# AtmegBROKE.net
KiCad netlist of a schematic drawn in EAGLE
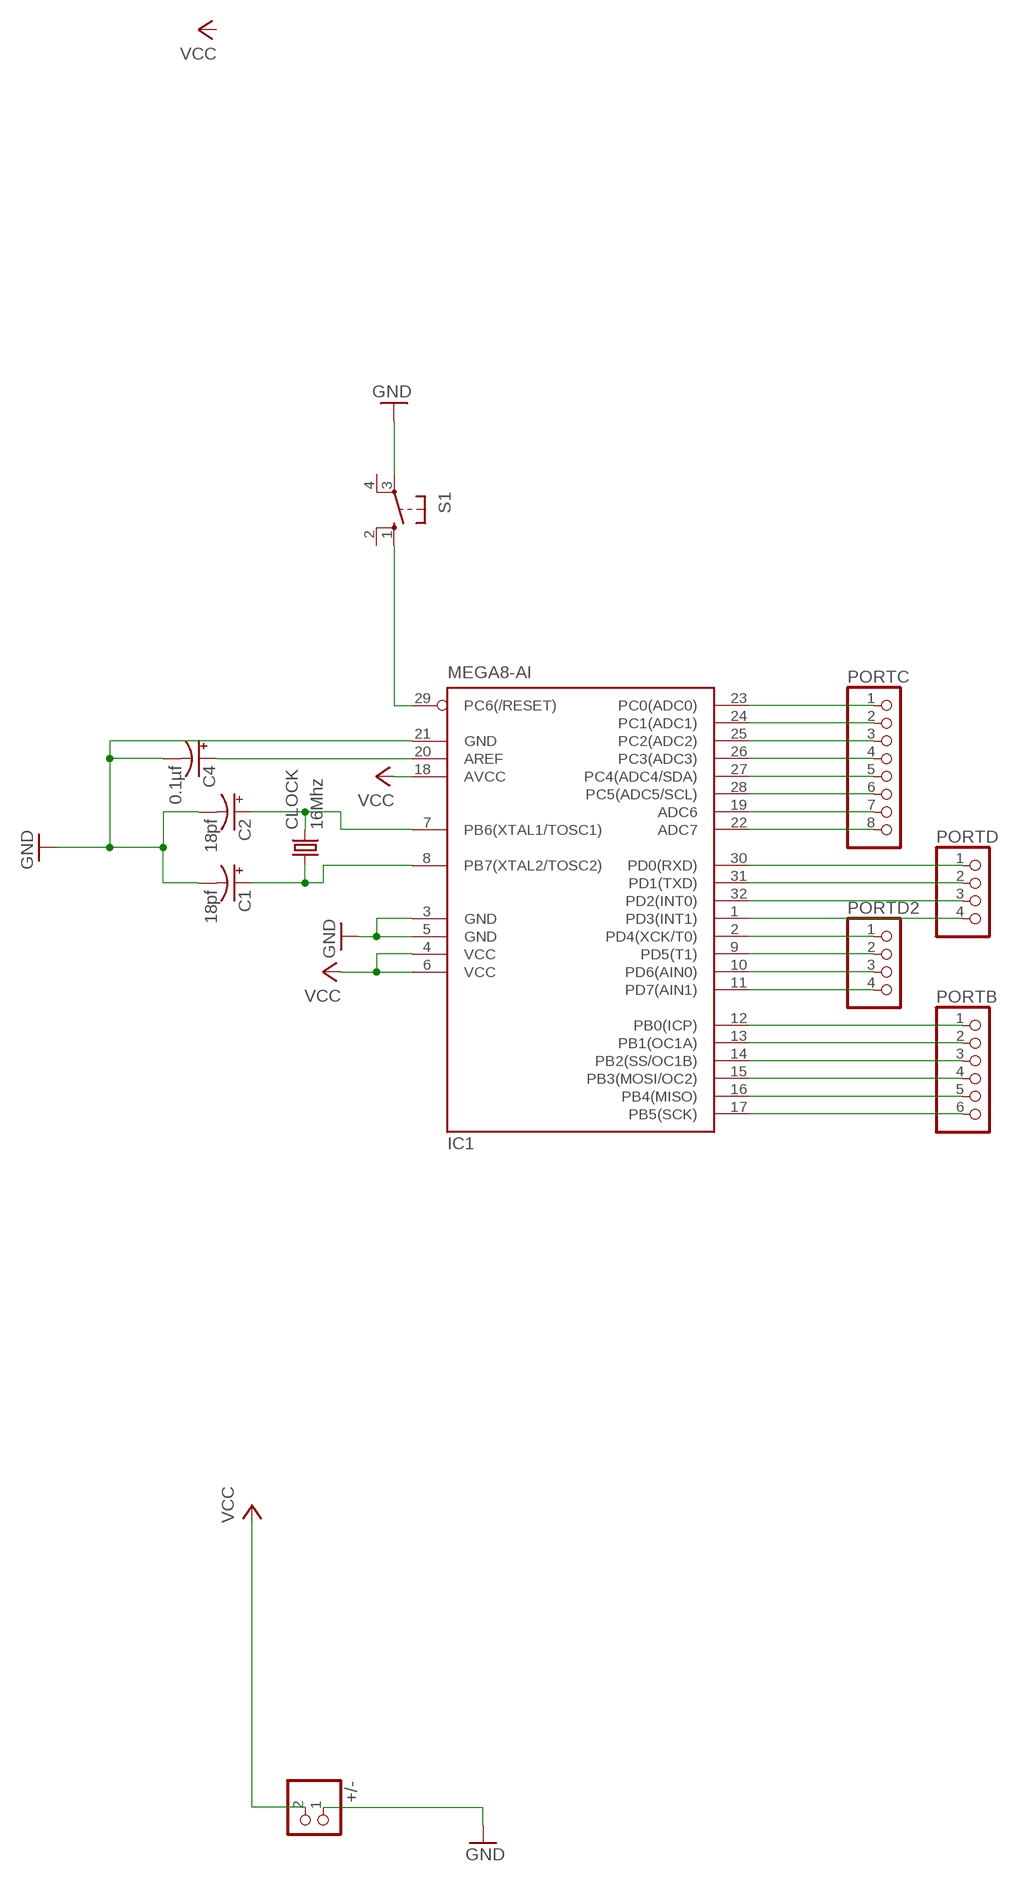
[diagram p0: schematic, sheet 1]

(export (version "E")
  (design (tool "Eeschema 10.0.6"))
  (components
    (comp (ref "+/-")
      (value "PINHD-1X2")
      (footprint "eagle-import:1X02")
      (libsource (lib "eagle-import") (part "PINHD-1X2"))
    )
    (comp (ref "C1")
      (value "18pf")
      (footprint "eagle-import:SMC_Z")
      (libsource (lib "eagle-import") (part "CPOL-USSMCZ"))
    )
    (comp (ref "C2")
      (value "18pf")
      (footprint "eagle-import:SMC_Z")
      (libsource (lib "eagle-import") (part "CPOL-USSMCZ"))
    )
    (comp (ref "C4")
      (value "0.1µf")
      (footprint "eagle-import:SMC_Z")
      (libsource (lib "eagle-import") (part "CPOL-USSMCZ"))
    )
    (comp (ref "CLOCK")
      (value "16Mhz")
      (footprint "eagle-import:HC49UP")
      (libsource (lib "eagle-import") (part "CRYSTALHC49UP"))
    )
    (comp (ref "IC1")
      (value "MEGA8-AI")
      (footprint "eagle-import:TQFP32-08")
      (fields (field (name "MPN") "ATMEGA8-16AU"))
      (libsource (lib "eagle-import") (part "MEGA8-AI"))
    )
    (comp (ref "PORTB")
      (value "PINHD-1X6")
      (footprint "eagle-import:1X06")
      (libsource (lib "eagle-import") (part "PINHD-1X6"))
    )
    (comp (ref "PORTC")
      (value "PINHD-1X8")
      (footprint "eagle-import:1X08")
      (libsource (lib "eagle-import") (part "PINHD-1X8"))
    )
    (comp (ref "PORTD")
      (value "PINHD-1X4")
      (footprint "eagle-import:1X04")
      (libsource (lib "eagle-import") (part "PINHD-1X4"))
    )
    (comp (ref "PORTD2")
      (value "PINHD-1X4")
      (footprint "eagle-import:1X04")
      (libsource (lib "eagle-import") (part "PINHD-1X4"))
    )
    (comp (ref "S1")
      (value "10-XX")
      (footprint "eagle-import:B3F-10XX")
      (fields (field (name "MPN") "B3F-1000"))
      (libsource (lib "eagle-import") (part "10-XX"))
    )
  )
  (nets
    (net (code "1") (name "GND") (class "Default")
      (node (ref "+/-") (pin "1") (pinfunction "1_1") (pintype "passive"))
      (node (ref "C1") (pin "-") (pinfunction "-_-") (pintype "passive"))
      (node (ref "C2") (pin "-") (pinfunction "-_-") (pintype "passive"))
      (node (ref "C4") (pin "-") (pinfunction "-_-") (pintype "passive"))
      (node (ref "IC1") (pin "21") (pinfunction "GND_21") (pintype "power_in"))
      (node (ref "IC1") (pin "3") (pinfunction "GND_3") (pintype "power_in"))
      (node (ref "IC1") (pin "5") (pinfunction "GND_5") (pintype "power_in"))
      (node (ref "S1") (pin "3") (pinfunction "P_3") (pintype "passive"))
    )
    (net (code "2") (name "Net-(IC1-ADC6)") (class "Default")
      (node (ref "IC1") (pin "19") (pinfunction "ADC6_19") (pintype "bidirectional"))
      (node (ref "PORTC") (pin "7") (pinfunction "7_7") (pintype "passive"))
    )
    (net (code "3") (name "Net-(IC1-ADC7)") (class "Default")
      (node (ref "IC1") (pin "22") (pinfunction "ADC7_22") (pintype "bidirectional"))
      (node (ref "PORTC") (pin "8") (pinfunction "8_8") (pintype "passive"))
    )
    (net (code "4") (name "Net-(IC1-AREF)") (class "Default")
      (node (ref "C4") (pin "+") (pinfunction "+_+") (pintype "passive"))
      (node (ref "IC1") (pin "20") (pinfunction "AREF_20") (pintype "passive"))
    )
    (net (code "5") (name "Net-(IC1-PB0(ICP))") (class "Default")
      (node (ref "IC1") (pin "12") (pinfunction "PB0(ICP)_12") (pintype "bidirectional"))
      (node (ref "PORTB") (pin "1") (pinfunction "1_1") (pintype "passive"))
    )
    (net (code "6") (name "Net-(IC1-PB1(OC1A))") (class "Default")
      (node (ref "IC1") (pin "13") (pinfunction "PB1(OC1A)_13") (pintype "bidirectional"))
      (node (ref "PORTB") (pin "2") (pinfunction "2_2") (pintype "passive"))
    )
    (net (code "7") (name "Net-(IC1-PB2(SS{slash}OC1B))") (class "Default")
      (node (ref "IC1") (pin "14") (pinfunction "PB2(SS/OC1B)_14") (pintype "bidirectional"))
      (node (ref "PORTB") (pin "3") (pinfunction "3_3") (pintype "passive"))
    )
    (net (code "8") (name "Net-(IC1-PB3(MOSI{slash}OC2))") (class "Default")
      (node (ref "IC1") (pin "15") (pinfunction "PB3(MOSI/OC2)_15") (pintype "bidirectional"))
      (node (ref "PORTB") (pin "4") (pinfunction "4_4") (pintype "passive"))
    )
    (net (code "9") (name "Net-(IC1-PB4(MISO))") (class "Default")
      (node (ref "IC1") (pin "16") (pinfunction "PB4(MISO)_16") (pintype "bidirectional"))
      (node (ref "PORTB") (pin "5") (pinfunction "5_5") (pintype "passive"))
    )
    (net (code "10") (name "Net-(IC1-PB5(SCK))") (class "Default")
      (node (ref "IC1") (pin "17") (pinfunction "PB5(SCK)_17") (pintype "bidirectional"))
      (node (ref "PORTB") (pin "6") (pinfunction "6_6") (pintype "passive"))
    )
    (net (code "11") (name "Net-(IC1-PB6(XTAL1{slash}TOSC1))") (class "Default")
      (node (ref "C2") (pin "+") (pinfunction "+_+") (pintype "passive"))
      (node (ref "CLOCK") (pin "2") (pinfunction "2_2") (pintype "passive"))
      (node (ref "IC1") (pin "7") (pinfunction "PB6(XTAL1/TOSC1)_7") (pintype "bidirectional"))
    )
    (net (code "12") (name "Net-(IC1-PB7(XTAL2{slash}TOSC2))") (class "Default")
      (node (ref "C1") (pin "+") (pinfunction "+_+") (pintype "passive"))
      (node (ref "CLOCK") (pin "1") (pinfunction "1_1") (pintype "passive"))
      (node (ref "IC1") (pin "8") (pinfunction "PB7(XTAL2/TOSC2)_8") (pintype "bidirectional"))
    )
    (net (code "13") (name "Net-(IC1-PC0(ADC0))") (class "Default")
      (node (ref "IC1") (pin "23") (pinfunction "PC0(ADC0)_23") (pintype "bidirectional"))
      (node (ref "PORTC") (pin "1") (pinfunction "1_1") (pintype "passive"))
    )
    (net (code "14") (name "Net-(IC1-PC1(ADC1))") (class "Default")
      (node (ref "IC1") (pin "24") (pinfunction "PC1(ADC1)_24") (pintype "bidirectional"))
      (node (ref "PORTC") (pin "2") (pinfunction "2_2") (pintype "passive"))
    )
    (net (code "15") (name "Net-(IC1-PC2(ADC2))") (class "Default")
      (node (ref "IC1") (pin "25") (pinfunction "PC2(ADC2)_25") (pintype "bidirectional"))
      (node (ref "PORTC") (pin "3") (pinfunction "3_3") (pintype "passive"))
    )
    (net (code "16") (name "Net-(IC1-PC3(ADC3))") (class "Default")
      (node (ref "IC1") (pin "26") (pinfunction "PC3(ADC3)_26") (pintype "bidirectional"))
      (node (ref "PORTC") (pin "4") (pinfunction "4_4") (pintype "passive"))
    )
    (net (code "17") (name "Net-(IC1-PC4(ADC4{slash}SDA))") (class "Default")
      (node (ref "IC1") (pin "27") (pinfunction "PC4(ADC4/SDA)_27") (pintype "bidirectional"))
      (node (ref "PORTC") (pin "5") (pinfunction "5_5") (pintype "passive"))
    )
    (net (code "18") (name "Net-(IC1-PC5(ADC5{slash}SCL))") (class "Default")
      (node (ref "IC1") (pin "28") (pinfunction "PC5(ADC5/SCL)_28") (pintype "bidirectional"))
      (node (ref "PORTC") (pin "6") (pinfunction "6_6") (pintype "passive"))
    )
    (net (code "19") (name "Net-(IC1-PC6({slash}RESET))") (class "Default")
      (node (ref "IC1") (pin "29") (pinfunction "PC6(/RESET)_29") (pintype "bidirectional"))
      (node (ref "S1") (pin "1") (pinfunction "S_1") (pintype "passive"))
    )
    (net (code "20") (name "Net-(IC1-PD0(RXD))") (class "Default")
      (node (ref "IC1") (pin "30") (pinfunction "PD0(RXD)_30") (pintype "bidirectional"))
      (node (ref "PORTD") (pin "1") (pinfunction "1_1") (pintype "passive"))
    )
    (net (code "21") (name "Net-(IC1-PD1(TXD))") (class "Default")
      (node (ref "IC1") (pin "31") (pinfunction "PD1(TXD)_31") (pintype "bidirectional"))
      (node (ref "PORTD") (pin "2") (pinfunction "2_2") (pintype "passive"))
    )
    (net (code "22") (name "Net-(IC1-PD2(INT0))") (class "Default")
      (node (ref "IC1") (pin "32") (pinfunction "PD2(INT0)_32") (pintype "bidirectional"))
      (node (ref "PORTD") (pin "3") (pinfunction "3_3") (pintype "passive"))
    )
    (net (code "23") (name "Net-(IC1-PD3(INT1))") (class "Default")
      (node (ref "IC1") (pin "1") (pinfunction "PD3(INT1)_1") (pintype "bidirectional"))
      (node (ref "PORTD") (pin "4") (pinfunction "4_4") (pintype "passive"))
    )
    (net (code "24") (name "Net-(IC1-PD4(XCK{slash}T0))") (class "Default")
      (node (ref "IC1") (pin "2") (pinfunction "PD4(XCK/T0)_2") (pintype "bidirectional"))
      (node (ref "PORTD2") (pin "1") (pinfunction "1_1") (pintype "passive"))
    )
    (net (code "25") (name "Net-(IC1-PD5(T1))") (class "Default")
      (node (ref "IC1") (pin "9") (pinfunction "PD5(T1)_9") (pintype "bidirectional"))
      (node (ref "PORTD2") (pin "2") (pinfunction "2_2") (pintype "passive"))
    )
    (net (code "26") (name "Net-(IC1-PD6(AIN0))") (class "Default")
      (node (ref "IC1") (pin "10") (pinfunction "PD6(AIN0)_10") (pintype "bidirectional"))
      (node (ref "PORTD2") (pin "3") (pinfunction "3_3") (pintype "passive"))
    )
    (net (code "27") (name "Net-(IC1-PD7(AIN1))") (class "Default")
      (node (ref "IC1") (pin "11") (pinfunction "PD7(AIN1)_11") (pintype "bidirectional"))
      (node (ref "PORTD2") (pin "4") (pinfunction "4_4") (pintype "passive"))
    )
    (net (code "28") (name "VCC") (class "Default")
      (node (ref "+/-") (pin "2") (pinfunction "2_2") (pintype "passive"))
      (node (ref "IC1") (pin "18") (pinfunction "AVCC_18") (pintype "power_in"))
      (node (ref "IC1") (pin "4") (pinfunction "VCC_4") (pintype "power_in"))
      (node (ref "IC1") (pin "6") (pinfunction "VCC_6") (pintype "power_in"))
    )
    (net (code "29") (name "unconnected-(S1-P1-Pad4)") (class "Default")
      (node (ref "S1") (pin "4") (pinfunction "P1_4") (pintype "passive"))
    )
    (net (code "30") (name "unconnected-(S1-S1-Pad2)") (class "Default")
      (node (ref "S1") (pin "2") (pinfunction "S1_2") (pintype "passive"))
    )
  )
)
